# main.net
KiCad netlist of a schematic drawn in Altium Designer
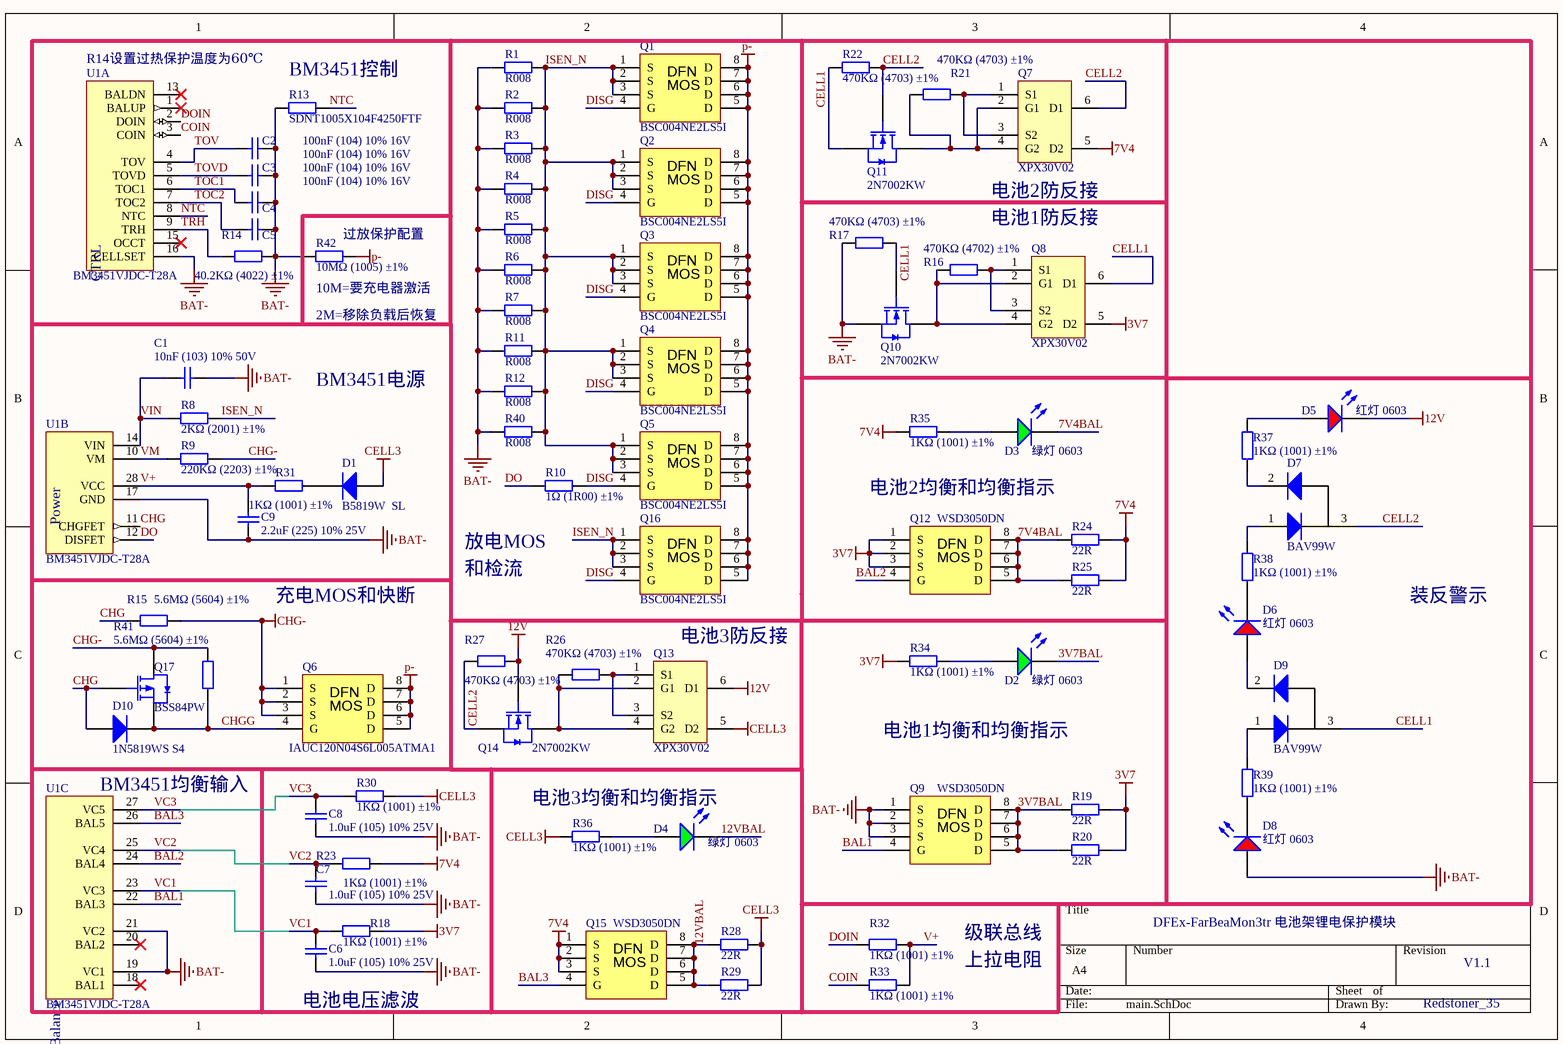
[diagram p0: main.SchDoc]

(export (version "E")
  (design (tool "Eeschema 10.0.6"))
  (components
    (comp (ref "C1")
      (value "10nF (103) 10% 50V")
      (footprint "0402_C")
      (description "贴片电容")
      (libsource (lib "Miscellaneous Devices LC") (part "0402 10nF (103) 10% 50V"))
    )
    (comp (ref "C2")
      (value "100nF (104) 10% 16V")
      (footprint "0402_C")
      (description "贴片电容")
      (libsource (lib "Miscellaneous Devices LC") (part "0402 100nF (104) 10% 16V"))
    )
    (comp (ref "C3")
      (value "100nF (104) 10% 16V")
      (footprint "0402_C")
      (description "贴片电容")
      (libsource (lib "Miscellaneous Devices LC") (part "0402 100nF (104) 10% 16V"))
    )
    (comp (ref "C4")
      (value "100nF (104) 10% 16V")
      (footprint "0402_C")
      (description "贴片电容")
      (libsource (lib "Miscellaneous Devices LC") (part "0402 100nF (104) 10% 16V"))
    )
    (comp (ref "C5")
      (value "100nF (104) 10% 16V")
      (footprint "0402_C")
      (description "贴片电容")
      (libsource (lib "Miscellaneous Devices LC") (part "0402 100nF (104) 10% 16V"))
    )
    (comp (ref "C6")
      (value "1.0uF (105) 10% 25V")
      (footprint "0402_C")
      (description "贴片电容")
      (libsource (lib "Miscellaneous Devices LC") (part "0402 1.0uF (105) 10% 25V"))
    )
    (comp (ref "C7")
      (value "1.0uF (105) 10% 25V")
      (footprint "0402_C")
      (description "贴片电容")
      (libsource (lib "Miscellaneous Devices LC") (part "0402 1.0uF (105) 10% 25V"))
    )
    (comp (ref "C8")
      (value "1.0uF (105) 10% 25V")
      (footprint "0402_C")
      (description "贴片电容")
      (libsource (lib "Miscellaneous Devices LC") (part "0402 1.0uF (105) 10% 25V"))
    )
    (comp (ref "C9")
      (value "2.2uF (225) 10% 25V")
      (footprint "0402_C")
      (description "贴片电容")
      (libsource (lib "Miscellaneous Devices LC") (part "0402 2.2nF (222) 10% 50V"))
    )
    (comp (ref "D1")
      (value "B5819W  SL")
      (footprint "SOD-123")
      (description "肖特基二极管")
      (libsource (lib "Miscellaneous Devices LC") (part "SOD-123 B5819W  SL"))
    )
    (comp (ref "D2")
      (value "绿灯 0603")
      (footprint "0603_LED_S1")
      (description "发光二极管")
      (libsource (lib "Miscellaneous Devices LC") (part "0603 绿灯"))
    )
    (comp (ref "D3")
      (value "绿灯 0603")
      (footprint "0603_LED_S1")
      (description "发光二极管")
      (libsource (lib "Miscellaneous Devices LC") (part "0603 绿灯"))
    )
    (comp (ref "D4")
      (value "绿灯 0603")
      (footprint "0603_LED_S1")
      (description "发光二极管")
      (libsource (lib "Miscellaneous Devices LC") (part "0603 绿灯"))
    )
    (comp (ref "D5")
      (value "红灯 0603")
      (footprint "0603_LED_S1")
      (description "发光二极管")
      (libsource (lib "Miscellaneous Devices LC") (part "0603 红灯"))
    )
    (comp (ref "D6")
      (value "红灯 0603")
      (footprint "0603_LED_S1")
      (description "发光二极管")
      (libsource (lib "Miscellaneous Devices LC") (part "0603 红灯"))
    )
    (comp (ref "D7")
      (value "BAV99W")
      (footprint "SC70-3")
      (description "开关二极管")
      (libsource (lib "Miscellaneous Devices LC") (part "SOT-23 BAV99 A7W"))
    )
    (comp (ref "D8")
      (value "红灯 0603")
      (footprint "0603_LED_S1")
      (description "发光二极管")
      (libsource (lib "Miscellaneous Devices LC") (part "0603 红灯"))
    )
    (comp (ref "D9")
      (value "BAV99W")
      (footprint "SC70-3")
      (description "开关二极管")
      (libsource (lib "Miscellaneous Devices LC") (part "SOT-23 BAV99 A7W"))
    )
    (comp (ref "D10")
      (value "1N5819WS S4")
      (footprint "SOD-323")
      (description "二极管")
      (libsource (lib "Miscellaneous Devices LC") (part "SOD-323 1N4148WS T4"))
    )
    (comp (ref "Q1")
      (value "BSC004NE2LS5I")
      (footprint "SON/DFN5x6(MOS)")
      (description "0.4mR OptiMOS 5 MOSFET")
      (libsource (lib "custom") (part "SON/DFN5x6 MOS"))
    )
    (comp (ref "Q2")
      (value "BSC004NE2LS5I")
      (footprint "SON/DFN5x6(MOS)")
      (description "0.4mR OptiMOS 5 MOSFET")
      (libsource (lib "custom") (part "SON/DFN5x6 MOS"))
    )
    (comp (ref "Q3")
      (value "BSC004NE2LS5I")
      (footprint "SON/DFN5x6(MOS)")
      (description "0.4mR OptiMOS 5 MOSFET")
      (libsource (lib "custom") (part "SON/DFN5x6 MOS"))
    )
    (comp (ref "Q4")
      (value "BSC004NE2LS5I")
      (footprint "SON/DFN5x6(MOS)")
      (description "0.4mR OptiMOS 5 MOSFET")
      (libsource (lib "custom") (part "SON/DFN5x6 MOS"))
    )
    (comp (ref "Q5")
      (value "BSC004NE2LS5I")
      (footprint "SON/DFN5x6(MOS)")
      (description "0.4mR OptiMOS 5 MOSFET")
      (libsource (lib "custom") (part "SON/DFN5x6 MOS"))
    )
    (comp (ref "Q6")
      (value "IAUC120N04S6L005ATMA1")
      (footprint "SON/DFN5x6(MOS)")
      (description "0.5mR 120A OptiMOS 6 Automotive grade MOSFET,SSO8(5x6) Package")
      (libsource (lib "custom") (part "SON/DFN5x6 MOS"))
    )
    (comp (ref "Q7")
      (value "XPX30V02")
      (footprint "EDFN3x3")
      (description "双N沟道MOSFET, DFN3x3 30V 40A 10mΩ")
      (libsource (lib "custom") (part "XPX10H03RX"))
    )
    (comp (ref "Q8")
      (value "XPX30V02")
      (footprint "EDFN3x3")
      (description "双N沟道MOSFET, DFN3x3 30V 40A 10mΩ")
      (libsource (lib "custom") (part "XPX10H03RX"))
    )
    (comp (ref "Q9")
      (value "WSD3050DN")
      (footprint "DFN-8_L3.0-W3.0-P0.65-BL")
      (description "PDFN3x3 20V 50A 5.8mΩ N-Ch MOSFET")
      (libsource (lib "custom") (part "SON/DFN5x6 MOS"))
    )
    (comp (ref "Q10")
      (value "2N7002KW")
      (footprint "SC70-3")
      (description "单N沟道MOSFET(场效应管)")
      (libsource (lib "Miscellaneous Devices LC") (part "2N7002 7002"))
    )
    (comp (ref "Q11")
      (value "2N7002KW")
      (footprint "SC70-3")
      (description "单N沟道MOSFET(场效应管)")
      (libsource (lib "Miscellaneous Devices LC") (part "2N7002 7002"))
    )
    (comp (ref "Q12")
      (value "WSD3050DN")
      (footprint "DFN-8_L3.0-W3.0-P0.65-BL")
      (description "PDFN3x3 20V 50A 5.8mΩ N-Ch MOSFET")
      (libsource (lib "custom") (part "SON/DFN5x6 MOS"))
    )
    (comp (ref "Q13")
      (value "XPX30V02")
      (footprint "EDFN3x3")
      (description "双N沟道MOSFET, DFN3x3 30V 40A 10mΩ")
      (libsource (lib "custom") (part "XPX10H03RX"))
    )
    (comp (ref "Q14")
      (value "2N7002KW")
      (footprint "SC70-3")
      (description "单N沟道MOSFET(场效应管)")
      (libsource (lib "Miscellaneous Devices LC") (part "2N7002 7002"))
    )
    (comp (ref "Q15")
      (value "WSD3050DN")
      (footprint "DFN-8_L3.0-W3.0-P0.65-BL")
      (description "PDFN3x3 20V 50A 5.8mΩ N-Ch MOSFET")
      (libsource (lib "custom") (part "SON/DFN5x6 MOS"))
    )
    (comp (ref "Q16")
      (value "BSC004NE2LS5I")
      (footprint "SON/DFN5x6(MOS)")
      (description "0.4mR OptiMOS 5 MOSFET")
      (libsource (lib "custom") (part "SON/DFN5x6 MOS"))
    )
    (comp (ref "Q17")
      (value "BSS84PW")
      (footprint "SC70-3")
      (description "MOS(场效应管)")
      (libsource (lib "Miscellaneous Devices LC") (part "SI2301CDS-T1-GE3"))
    )
    (comp (ref "R1")
      (value "R008")
      (footprint "1206R")
      (description "Resistor")
      (fields (field (name "PUBLISHER") "Altium Limited"))
      (libsource (lib "山猫的集成库20190318") (part "Res"))
    )
    (comp (ref "R2")
      (value "R008")
      (footprint "1206R")
      (description "Resistor")
      (fields (field (name "PUBLISHER") "Altium Limited"))
      (libsource (lib "山猫的集成库20190318") (part "Res"))
    )
    (comp (ref "R3")
      (value "R008")
      (footprint "1206R")
      (description "Resistor")
      (fields (field (name "PUBLISHER") "Altium Limited"))
      (libsource (lib "山猫的集成库20190318") (part "Res"))
    )
    (comp (ref "R4")
      (value "R008")
      (footprint "1206R")
      (description "Resistor")
      (fields (field (name "PUBLISHER") "Altium Limited"))
      (libsource (lib "山猫的集成库20190318") (part "Res"))
    )
    (comp (ref "R5")
      (value "R008")
      (footprint "1206R")
      (description "Resistor")
      (fields (field (name "PUBLISHER") "Altium Limited"))
      (libsource (lib "山猫的集成库20190318") (part "Res"))
    )
    (comp (ref "R6")
      (value "R008")
      (footprint "1206R")
      (description "Resistor")
      (fields (field (name "PUBLISHER") "Altium Limited"))
      (libsource (lib "山猫的集成库20190318") (part "Res"))
    )
    (comp (ref "R7")
      (value "R008")
      (footprint "1206R")
      (description "Resistor")
      (fields (field (name "PUBLISHER") "Altium Limited"))
      (libsource (lib "山猫的集成库20190318") (part "Res"))
    )
    (comp (ref "R8")
      (value "2KΩ (2001) ±1%")
      (footprint "0402_R")
      (description "贴片电阻")
      (libsource (lib "Miscellaneous Devices LC") (part "0402 2KΩ (2001) 1%"))
    )
    (comp (ref "R9")
      (value "220KΩ (2203) ±1%")
      (footprint "0402_R")
      (description "贴片电阻")
      (libsource (lib "Miscellaneous Devices LC") (part "0402 220KΩ (2203) 1%"))
    )
    (comp (ref "R10")
      (value "1Ω (1R00) ±1%")
      (footprint "0402_R")
      (description "贴片电阻")
      (libsource (lib "Miscellaneous Devices LC") (part "0402 1Ω (1R00) 1%"))
    )
    (comp (ref "R11")
      (value "R008")
      (footprint "1206R")
      (description "Resistor")
      (fields (field (name "PUBLISHER") "Altium Limited"))
      (libsource (lib "山猫的集成库20190318") (part "Res"))
    )
    (comp (ref "R12")
      (value "R008")
      (footprint "1206R")
      (description "Resistor")
      (fields (field (name "PUBLISHER") "Altium Limited"))
      (libsource (lib "山猫的集成库20190318") (part "Res"))
    )
    (comp (ref "R13")
      (value "SDNT1005X104F4250FTF")
      (footprint "0402_R")
      (description "贴片NTC热敏电阻 100KΩ (1003) ±1% B4250")
      (libsource (lib "Miscellaneous Devices LC") (part "0402 100KΩ (1003) 1%"))
    )
    (comp (ref "R14")
      (value "40.2KΩ (4022) ±1%")
      (footprint "0402_R")
      (description "贴片电阻")
      (libsource (lib "Miscellaneous Devices LC") (part "0402 56KΩ (5602) 1%"))
    )
    (comp (ref "R15")
      (value "5.6MΩ (5604) ±1%")
      (footprint "0402_R")
      (description "贴片电阻")
      (libsource (lib "") (part "0402 1MΩ (1004) 1%_1"))
    )
    (comp (ref "R16")
      (value "470KΩ (4702) ±1%")
      (footprint "0402_R")
      (description "贴片电阻")
      (libsource (lib "Miscellaneous Devices LC") (part "0402 20KΩ (2002) 1%"))
    )
    (comp (ref "R17")
      (value "470KΩ (4703) ±1%")
      (footprint "0402_R")
      (description "贴片电阻")
      (libsource (lib "Miscellaneous Devices LC") (part "0402 470KΩ (4703) 1%"))
    )
    (comp (ref "R18")
      (value "1KΩ (1001) ±1%")
      (footprint "0402_R")
      (description "贴片电阻")
      (libsource (lib "Miscellaneous Devices LC") (part "0402 1KΩ (1001) 1%"))
    )
    (comp (ref "R19")
      (value "22R")
      (footprint "1210R")
      (description "Resistor")
      (fields (field (name "PUBLISHER") "Altium Limited"))
      (libsource (lib "山猫的集成库20190318") (part "Res"))
    )
    (comp (ref "R20")
      (value "22R")
      (footprint "1210R")
      (description "Resistor")
      (fields (field (name "PUBLISHER") "Altium Limited"))
      (libsource (lib "山猫的集成库20190318") (part "Res"))
    )
    (comp (ref "R21")
      (value "470KΩ (4703) ±1%")
      (footprint "0402_R")
      (description "贴片电阻")
      (libsource (lib "Miscellaneous Devices LC") (part "0402 470KΩ (4703) 1%"))
    )
    (comp (ref "R22")
      (value "470KΩ (4703) ±1%")
      (footprint "0402_R")
      (description "贴片电阻")
      (libsource (lib "Miscellaneous Devices LC") (part "0402 470KΩ (4703) 1%"))
    )
    (comp (ref "R23")
      (value "1KΩ (1001) ±1%")
      (footprint "0402_R")
      (description "贴片电阻")
      (libsource (lib "Miscellaneous Devices LC") (part "0402 1KΩ (1001) 1%"))
    )
    (comp (ref "R24")
      (value "22R")
      (footprint "1210R")
      (description "Resistor")
      (fields (field (name "PUBLISHER") "Altium Limited"))
      (libsource (lib "山猫的集成库20190318") (part "Res"))
    )
    (comp (ref "R25")
      (value "22R")
      (footprint "1210R")
      (description "Resistor")
      (fields (field (name "PUBLISHER") "Altium Limited"))
      (libsource (lib "山猫的集成库20190318") (part "Res"))
    )
    (comp (ref "R26")
      (value "470KΩ (4703) ±1%")
      (footprint "0402_R")
      (description "贴片电阻")
      (libsource (lib "Miscellaneous Devices LC") (part "0402 470KΩ (4703) 1%"))
    )
    (comp (ref "R27")
      (value "470KΩ (4703) ±1%")
      (footprint "0402_R")
      (description "贴片电阻")
      (libsource (lib "Miscellaneous Devices LC") (part "0402 470KΩ (4703) 1%"))
    )
    (comp (ref "R28")
      (value "22R")
      (footprint "1210R")
      (description "Resistor")
      (fields (field (name "PUBLISHER") "Altium Limited"))
      (libsource (lib "山猫的集成库20190318") (part "Res"))
    )
    (comp (ref "R29")
      (value "22R")
      (footprint "1210R")
      (description "Resistor")
      (fields (field (name "PUBLISHER") "Altium Limited"))
      (libsource (lib "山猫的集成库20190318") (part "Res"))
    )
    (comp (ref "R30")
      (value "1KΩ (1001) ±1%")
      (footprint "0402_R")
      (description "贴片电阻")
      (libsource (lib "Miscellaneous Devices LC") (part "0402 1KΩ (1001) 1%"))
    )
    (comp (ref "R31")
      (value "1KΩ (1001) ±1%")
      (footprint "0402_R")
      (description "贴片电阻")
      (libsource (lib "Miscellaneous Devices LC") (part "0402 1KΩ (1001) 1%"))
    )
    (comp (ref "R32")
      (value "1KΩ (1001) ±1%")
      (footprint "0402_R")
      (description "贴片电阻")
      (libsource (lib "Miscellaneous Devices LC") (part "0402 1KΩ (1001) 1%"))
    )
    (comp (ref "R33")
      (value "1KΩ (1001) ±1%")
      (footprint "0402_R")
      (description "贴片电阻")
      (libsource (lib "Miscellaneous Devices LC") (part "0402 1KΩ (1001) 1%"))
    )
    (comp (ref "R34")
      (value "1KΩ (1001) ±1%")
      (footprint "0402_R")
      (description "贴片电阻")
      (libsource (lib "Miscellaneous Devices LC") (part "0402 1KΩ (1001) 1%"))
    )
    (comp (ref "R35")
      (value "1KΩ (1001) ±1%")
      (footprint "0402_R")
      (description "贴片电阻")
      (libsource (lib "Miscellaneous Devices LC") (part "0402 1KΩ (1001) 1%"))
    )
    (comp (ref "R36")
      (value "1KΩ (1001) ±1%")
      (footprint "0402_R")
      (description "贴片电阻")
      (libsource (lib "Miscellaneous Devices LC") (part "0402 1KΩ (1001) 1%"))
    )
    (comp (ref "R37")
      (value "1KΩ (1001) ±1%")
      (footprint "0402_R")
      (description "贴片电阻")
      (libsource (lib "") (part "0402 1KΩ (1001) 1%_1"))
    )
    (comp (ref "R38")
      (value "1KΩ (1001) ±1%")
      (footprint "0402_R")
      (description "贴片电阻")
      (libsource (lib "") (part "0402 1KΩ (1001) 1%_1"))
    )
    (comp (ref "R39")
      (value "1KΩ (1001) ±1%")
      (footprint "0402_R")
      (description "贴片电阻")
      (libsource (lib "") (part "0402 1KΩ (1001) 1%_1"))
    )
    (comp (ref "R40")
      (value "R008")
      (footprint "1206R")
      (description "Resistor")
      (fields (field (name "PUBLISHER") "Altium Limited"))
      (libsource (lib "山猫的集成库20190318") (part "Res"))
    )
    (comp (ref "R41")
      (value "5.6MΩ (5604) ±1%")
      (footprint "0402_R")
      (description "贴片电阻")
      (libsource (lib "Miscellaneous Devices LC") (part "0402 1MΩ (1004) 1%"))
    )
    (comp (ref "R42")
      (value "10MΩ (1005) ±1%")
      (footprint "0402_R")
      (description "贴片电阻")
      (libsource (lib "Miscellaneous Devices LC") (part "0402 10MΩ (1005) 1%"))
    )
    (comp (ref "U1")
      (value "BM3451VJDC-T28A")
      (footprint "TSSOP28-BM3451")
      (description "2-5串全功能锂电池保护IC，支持级联功能")
      (libsource (lib "custom") (part "BM3451-T28A"))
    )
  )
  (nets
    (net (code "1") (name "/3V7BAL") (class "Default")
      (node (ref "D2") (pin "K") (pinfunction "K_K") (pintype "passive"))
      (node (ref "Q9") (pin "5") (pinfunction "D_5") (pintype "passive"))
      (node (ref "Q9") (pin "6") (pinfunction "D_6") (pintype "passive"))
      (node (ref "Q9") (pin "7") (pinfunction "D_7") (pintype "passive"))
      (node (ref "Q9") (pin "8") (pinfunction "D_8") (pintype "passive"))
      (node (ref "R19") (pin "2") (pinfunction "2_2") (pintype "passive"))
      (node (ref "R20") (pin "2") (pinfunction "2_2") (pintype "passive"))
    )
    (net (code "2") (name "/7V4BAL") (class "Default")
      (node (ref "D3") (pin "K") (pinfunction "K_K") (pintype "passive"))
      (node (ref "Q12") (pin "5") (pinfunction "D_5") (pintype "passive"))
      (node (ref "Q12") (pin "6") (pinfunction "D_6") (pintype "passive"))
      (node (ref "Q12") (pin "7") (pinfunction "D_7") (pintype "passive"))
      (node (ref "Q12") (pin "8") (pinfunction "D_8") (pintype "passive"))
      (node (ref "R24") (pin "2") (pinfunction "2_2") (pintype "passive"))
      (node (ref "R25") (pin "2") (pinfunction "2_2") (pintype "passive"))
    )
    (net (code "3") (name "/12VBAL") (class "Default")
      (node (ref "D4") (pin "K") (pinfunction "K_K") (pintype "passive"))
      (node (ref "Q15") (pin "5") (pinfunction "D_5") (pintype "passive"))
      (node (ref "Q15") (pin "6") (pinfunction "D_6") (pintype "passive"))
      (node (ref "Q15") (pin "7") (pinfunction "D_7") (pintype "passive"))
      (node (ref "Q15") (pin "8") (pinfunction "D_8") (pintype "passive"))
      (node (ref "R28") (pin "2") (pinfunction "2_2") (pintype "passive"))
      (node (ref "R29") (pin "2") (pinfunction "2_2") (pintype "passive"))
    )
    (net (code "4") (name "/BAL1") (class "Default")
      (node (ref "Q9") (pin "4") (pinfunction "G_4") (pintype "passive"))
      (node (ref "U1") (pin "22") (pinfunction "BAL3_22") (pintype "power_in"))
    )
    (net (code "5") (name "/BAL2") (class "Default")
      (node (ref "Q12") (pin "4") (pinfunction "G_4") (pintype "passive"))
      (node (ref "U1") (pin "24") (pinfunction "BAL4_24") (pintype "power_in"))
    )
    (net (code "6") (name "/BAL3") (class "Default")
      (node (ref "Q15") (pin "4") (pinfunction "G_4") (pintype "passive"))
      (node (ref "U1") (pin "26") (pinfunction "BAL5_26") (pintype "power_in"))
    )
    (net (code "7") (name "/CELL1") (class "Default")
      (node (ref "D9") (pin "3") (pinfunction "K_3") (pintype "passive"))
      (node (ref "Q10") (pin "1") (pinfunction "G_1") (pintype "passive"))
      (node (ref "Q11") (pin "2") (pinfunction "S_2") (pintype "passive"))
      (node (ref "Q8") (pin "6") (pinfunction "D1_6") (pintype "passive"))
      (node (ref "R17") (pin "2") (pinfunction "2_2") (pintype "passive"))
      (node (ref "R22") (pin "1") (pinfunction "1_1") (pintype "passive"))
    )
    (net (code "8") (name "/CELL2") (class "Default")
      (node (ref "D7") (pin "3") (pinfunction "K_3") (pintype "passive"))
      (node (ref "Q11") (pin "1") (pinfunction "G_1") (pintype "passive"))
      (node (ref "Q14") (pin "2") (pinfunction "S_2") (pintype "passive"))
      (node (ref "Q7") (pin "6") (pinfunction "D1_6") (pintype "passive"))
      (node (ref "R22") (pin "2") (pinfunction "2_2") (pintype "passive"))
      (node (ref "R27") (pin "1") (pinfunction "1_1") (pintype "passive"))
    )
    (net (code "9") (name "/CHG") (class "Default")
      (node (ref "D10") (pin "1") (pinfunction "A_1") (pintype "passive"))
      (node (ref "Q17") (pin "1") (pinfunction "G_1") (pintype "passive"))
      (node (ref "R15") (pin "1") (pinfunction "1_1") (pintype "passive"))
      (node (ref "U1") (pin "11") (pinfunction "CHGFET_11") (pintype "output"))
    )
    (net (code "10") (name "/CHGG") (class "Default")
      (node (ref "D10") (pin "2") (pinfunction "K_2") (pintype "passive"))
      (node (ref "Q17") (pin "2") (pinfunction "S_2") (pintype "passive"))
      (node (ref "Q6") (pin "4") (pinfunction "G_4") (pintype "passive"))
      (node (ref "R41") (pin "1") (pinfunction "1_1") (pintype "passive"))
    )
    (net (code "11") (name "/COIN") (class "Default")
      (node (ref "R33") (pin "1") (pinfunction "1_1") (pintype "passive"))
      (node (ref "U1") (pin "3") (pinfunction "COIN_3") (pintype "bidirectional"))
    )
    (net (code "12") (name "/DISG") (class "Default")
      (node (ref "Q1") (pin "4") (pinfunction "G_4") (pintype "passive"))
      (node (ref "Q16") (pin "4") (pinfunction "G_4") (pintype "passive"))
      (node (ref "Q2") (pin "4") (pinfunction "G_4") (pintype "passive"))
      (node (ref "Q3") (pin "4") (pinfunction "G_4") (pintype "passive"))
      (node (ref "Q4") (pin "4") (pinfunction "G_4") (pintype "passive"))
      (node (ref "Q5") (pin "4") (pinfunction "G_4") (pintype "passive"))
      (node (ref "R10") (pin "2") (pinfunction "2_2") (pintype "passive"))
    )
    (net (code "13") (name "/DO") (class "Default")
      (node (ref "R10") (pin "1") (pinfunction "1_1") (pintype "passive"))
      (node (ref "U1") (pin "12") (pinfunction "DISFET_12") (pintype "output"))
    )
    (net (code "14") (name "/DOIN") (class "Default")
      (node (ref "R32") (pin "1") (pinfunction "1_1") (pintype "passive"))
      (node (ref "U1") (pin "2") (pinfunction "DOIN_2") (pintype "bidirectional"))
    )
    (net (code "15") (name "/ISEN_N") (class "Default")
      (node (ref "Q1") (pin "1") (pinfunction "S_1") (pintype "passive"))
      (node (ref "Q1") (pin "2") (pinfunction "S_2") (pintype "passive"))
      (node (ref "Q1") (pin "3") (pinfunction "S_3") (pintype "passive"))
      (node (ref "Q16") (pin "1") (pinfunction "S_1") (pintype "passive"))
      (node (ref "Q16") (pin "2") (pinfunction "S_2") (pintype "passive"))
      (node (ref "Q16") (pin "3") (pinfunction "S_3") (pintype "passive"))
      (node (ref "Q2") (pin "1") (pinfunction "S_1") (pintype "passive"))
      (node (ref "Q2") (pin "2") (pinfunction "S_2") (pintype "passive"))
      (node (ref "Q2") (pin "3") (pinfunction "S_3") (pintype "passive"))
      (node (ref "Q3") (pin "1") (pinfunction "S_1") (pintype "passive"))
      (node (ref "Q3") (pin "2") (pinfunction "S_2") (pintype "passive"))
      (node (ref "Q3") (pin "3") (pinfunction "S_3") (pintype "passive"))
      (node (ref "Q4") (pin "1") (pinfunction "S_1") (pintype "passive"))
      (node (ref "Q4") (pin "2") (pinfunction "S_2") (pintype "passive"))
      (node (ref "Q4") (pin "3") (pinfunction "S_3") (pintype "passive"))
      (node (ref "Q5") (pin "1") (pinfunction "S_1") (pintype "passive"))
      (node (ref "Q5") (pin "2") (pinfunction "S_2") (pintype "passive"))
      (node (ref "Q5") (pin "3") (pinfunction "S_3") (pintype "passive"))
      (node (ref "R1") (pin "1") (pinfunction "1_1") (pintype "passive"))
      (node (ref "R11") (pin "1") (pinfunction "1_1") (pintype "passive"))
      (node (ref "R12") (pin "1") (pinfunction "1_1") (pintype "passive"))
      (node (ref "R2") (pin "1") (pinfunction "1_1") (pintype "passive"))
      (node (ref "R3") (pin "1") (pinfunction "1_1") (pintype "passive"))
      (node (ref "R4") (pin "1") (pinfunction "1_1") (pintype "passive"))
      (node (ref "R40") (pin "1") (pinfunction "1_1") (pintype "passive"))
      (node (ref "R5") (pin "1") (pinfunction "1_1") (pintype "passive"))
      (node (ref "R6") (pin "1") (pinfunction "1_1") (pintype "passive"))
      (node (ref "R7") (pin "1") (pinfunction "1_1") (pintype "passive"))
      (node (ref "R8") (pin "2") (pinfunction "2_2") (pintype "passive"))
    )
    (net (code "16") (name "/NTC") (class "Default")
      (node (ref "R13") (pin "1") (pinfunction "1_1") (pintype "passive"))
      (node (ref "U1") (pin "8") (pinfunction "NTC_8") (pintype "passive"))
    )
    (net (code "17") (name "/TOC1") (class "Default")
      (node (ref "C4") (pin "1") (pinfunction "1_1") (pintype "passive"))
      (node (ref "U1") (pin "6") (pinfunction "TOC1_6") (pintype "passive"))
    )
    (net (code "18") (name "/TOC2") (class "Default")
      (node (ref "C5") (pin "1") (pinfunction "1_1") (pintype "passive"))
      (node (ref "U1") (pin "7") (pinfunction "TOC2_7") (pintype "passive"))
    )
    (net (code "19") (name "/TOV") (class "Default")
      (node (ref "C2") (pin "1") (pinfunction "1_1") (pintype "passive"))
      (node (ref "U1") (pin "4") (pinfunction "TOV_4") (pintype "passive"))
    )
    (net (code "20") (name "/TOVD") (class "Default")
      (node (ref "C3") (pin "1") (pinfunction "1_1") (pintype "passive"))
      (node (ref "U1") (pin "5") (pinfunction "TOVD_5") (pintype "passive"))
    )
    (net (code "21") (name "/TRH") (class "Default")
      (node (ref "R14") (pin "1") (pinfunction "1_1") (pintype "passive"))
      (node (ref "U1") (pin "9") (pinfunction "TRH_9") (pintype "passive"))
    )
    (net (code "22") (name "/V+") (class "Default")
      (node (ref "C9") (pin "2") (pinfunction "2_2") (pintype "passive"))
      (node (ref "R31") (pin "1") (pinfunction "1_1") (pintype "passive"))
      (node (ref "R32") (pin "2") (pinfunction "2_2") (pintype "passive"))
      (node (ref "R33") (pin "2") (pinfunction "2_2") (pintype "passive"))
      (node (ref "U1") (pin "28") (pinfunction "VCC_28") (pintype "power_in"))
    )
    (net (code "23") (name "/VC1") (class "Default")
      (node (ref "C6") (pin "2") (pinfunction "2_2") (pintype "passive"))
      (node (ref "R18") (pin "1") (pinfunction "1_1") (pintype "passive"))
      (node (ref "U1") (pin "23") (pinfunction "VC3_23") (pintype "power_in"))
    )
    (net (code "24") (name "/VC2") (class "Default")
      (node (ref "C7") (pin "2") (pinfunction "2_2") (pintype "passive"))
      (node (ref "R23") (pin "1") (pinfunction "1_1") (pintype "passive"))
      (node (ref "U1") (pin "25") (pinfunction "VC4_25") (pintype "power_in"))
    )
    (net (code "25") (name "/VC3") (class "Default")
      (node (ref "C8") (pin "2") (pinfunction "2_2") (pintype "passive"))
      (node (ref "R30") (pin "1") (pinfunction "1_1") (pintype "passive"))
      (node (ref "U1") (pin "27") (pinfunction "VC5_27") (pintype "power_in"))
    )
    (net (code "26") (name "/VIN") (class "Default")
      (node (ref "C1") (pin "1") (pinfunction "1_1") (pintype "passive"))
      (node (ref "R8") (pin "1") (pinfunction "1_1") (pintype "passive"))
      (node (ref "U1") (pin "14") (pinfunction "VIN_14") (pintype "power_in"))
    )
    (net (code "27") (name "/VM") (class "Default")
      (node (ref "R9") (pin "1") (pinfunction "1_1") (pintype "passive"))
      (node (ref "U1") (pin "10") (pinfunction "VM_10") (pintype "passive"))
    )
    (net (code "28") (name "3V7") (class "Default")
      (node (ref "Q12") (pin "1") (pinfunction "S_1") (pintype "passive"))
      (node (ref "Q12") (pin "2") (pinfunction "S_2") (pintype "passive"))
      (node (ref "Q12") (pin "3") (pinfunction "S_3") (pintype "passive"))
      (node (ref "Q8") (pin "5") (pinfunction "D2_5") (pintype "passive"))
      (node (ref "R18") (pin "2") (pinfunction "2_2") (pintype "passive"))
      (node (ref "R19") (pin "1") (pinfunction "1_1") (pintype "passive"))
      (node (ref "R20") (pin "1") (pinfunction "1_1") (pintype "passive"))
      (node (ref "R34") (pin "1") (pinfunction "1_1") (pintype "passive"))
    )
    (net (code "29") (name "7V4") (class "Default")
      (node (ref "Q15") (pin "1") (pinfunction "S_1") (pintype "passive"))
      (node (ref "Q15") (pin "2") (pinfunction "S_2") (pintype "passive"))
      (node (ref "Q15") (pin "3") (pinfunction "S_3") (pintype "passive"))
      (node (ref "Q7") (pin "5") (pinfunction "D2_5") (pintype "passive"))
      (node (ref "R23") (pin "2") (pinfunction "2_2") (pintype "passive"))
      (node (ref "R24") (pin "1") (pinfunction "1_1") (pintype "passive"))
      (node (ref "R25") (pin "1") (pinfunction "1_1") (pintype "passive"))
      (node (ref "R35") (pin "1") (pinfunction "1_1") (pintype "passive"))
    )
    (net (code "30") (name "12V") (class "Default")
      (node (ref "D5") (pin "K") (pinfunction "K_K") (pintype "passive"))
      (node (ref "Q13") (pin "6") (pinfunction "D1_6") (pintype "passive"))
      (node (ref "Q14") (pin "1") (pinfunction "G_1") (pintype "passive"))
      (node (ref "R27") (pin "2") (pinfunction "2_2") (pintype "passive"))
    )
    (net (code "31") (name "BAT-") (class "Default")
      (node (ref "C1") (pin "2") (pinfunction "2_2") (pintype "passive"))
      (node (ref "C2") (pin "2") (pinfunction "2_2") (pintype "passive"))
      (node (ref "C3") (pin "2") (pinfunction "2_2") (pintype "passive"))
      (node (ref "C4") (pin "2") (pinfunction "2_2") (pintype "passive"))
      (node (ref "C5") (pin "2") (pinfunction "2_2") (pintype "passive"))
      (node (ref "C6") (pin "1") (pinfunction "1_1") (pintype "passive"))
      (node (ref "C7") (pin "1") (pinfunction "1_1") (pintype "passive"))
      (node (ref "C8") (pin "1") (pinfunction "1_1") (pintype "passive"))
      (node (ref "C9") (pin "1") (pinfunction "1_1") (pintype "passive"))
      (node (ref "D8") (pin "A") (pinfunction "A_A") (pintype "passive"))
      (node (ref "Q10") (pin "2") (pinfunction "S_2") (pintype "passive"))
      (node (ref "Q9") (pin "1") (pinfunction "S_1") (pintype "passive"))
      (node (ref "Q9") (pin "2") (pinfunction "S_2") (pintype "passive"))
      (node (ref "Q9") (pin "3") (pinfunction "S_3") (pintype "passive"))
      (node (ref "R1") (pin "2") (pinfunction "2_2") (pintype "passive"))
      (node (ref "R11") (pin "2") (pinfunction "2_2") (pintype "passive"))
      (node (ref "R12") (pin "2") (pinfunction "2_2") (pintype "passive"))
      (node (ref "R13") (pin "2") (pinfunction "2_2") (pintype "passive"))
      (node (ref "R14") (pin "2") (pinfunction "2_2") (pintype "passive"))
      (node (ref "R17") (pin "1") (pinfunction "1_1") (pintype "passive"))
      (node (ref "R2") (pin "2") (pinfunction "2_2") (pintype "passive"))
      (node (ref "R3") (pin "2") (pinfunction "2_2") (pintype "passive"))
      (node (ref "R4") (pin "2") (pinfunction "2_2") (pintype "passive"))
      (node (ref "R40") (pin "2") (pinfunction "2_2") (pintype "passive"))
      (node (ref "R42") (pin "1") (pinfunction "1_1") (pintype "passive"))
      (node (ref "R5") (pin "2") (pinfunction "2_2") (pintype "passive"))
      (node (ref "R6") (pin "2") (pinfunction "2_2") (pintype "passive"))
      (node (ref "R7") (pin "2") (pinfunction "2_2") (pintype "passive"))
      (node (ref "U1") (pin "16") (pinfunction "CELLSET_16") (pintype "passive"))
      (node (ref "U1") (pin "17") (pinfunction "GND_17") (pintype "passive"))
      (node (ref "U1") (pin "19") (pinfunction "VC1_19") (pintype "power_in"))
      (node (ref "U1") (pin "21") (pinfunction "VC2_21") (pintype "power_in"))
    )
    (net (code "32") (name "CELL3") (class "Default")
      (node (ref "D1") (pin "1") (pinfunction "A_1") (pintype "passive"))
      (node (ref "Q13") (pin "5") (pinfunction "D2_5") (pintype "passive"))
      (node (ref "R28") (pin "1") (pinfunction "1_1") (pintype "passive"))
      (node (ref "R29") (pin "1") (pinfunction "1_1") (pintype "passive"))
      (node (ref "R30") (pin "2") (pinfunction "2_2") (pintype "passive"))
      (node (ref "R36") (pin "1") (pinfunction "1_1") (pintype "passive"))
    )
    (net (code "33") (name "CHG-") (class "Default")
      (node (ref "Q17") (pin "3") (pinfunction "D_3") (pintype "passive"))
      (node (ref "Q6") (pin "1") (pinfunction "S_1") (pintype "passive"))
      (node (ref "Q6") (pin "2") (pinfunction "S_2") (pintype "passive"))
      (node (ref "Q6") (pin "3") (pinfunction "S_3") (pintype "passive"))
      (node (ref "R15") (pin "2") (pinfunction "2_2") (pintype "passive"))
      (node (ref "R41") (pin "2") (pinfunction "2_2") (pintype "passive"))
      (node (ref "R9") (pin "2") (pinfunction "2_2") (pintype "passive"))
    )
    (net (code "34") (name "Net-(D1-K)") (class "Default")
      (node (ref "D1") (pin "2") (pinfunction "K_2") (pintype "passive"))
      (node (ref "R31") (pin "2") (pinfunction "2_2") (pintype "passive"))
    )
    (net (code "35") (name "Net-(D2-PadA)") (class "Default")
      (node (ref "D2") (pin "A") (pinfunction "A_A") (pintype "passive"))
      (node (ref "R34") (pin "2") (pinfunction "2_2") (pintype "passive"))
    )
    (net (code "36") (name "Net-(D3-PadA)") (class "Default")
      (node (ref "D3") (pin "A") (pinfunction "A_A") (pintype "passive"))
      (node (ref "R35") (pin "2") (pinfunction "2_2") (pintype "passive"))
    )
    (net (code "37") (name "Net-(D4-PadA)") (class "Default")
      (node (ref "D4") (pin "A") (pinfunction "A_A") (pintype "passive"))
      (node (ref "R36") (pin "2") (pinfunction "2_2") (pintype "passive"))
    )
    (net (code "38") (name "Net-(D5-PadA)") (class "Default")
      (node (ref "D5") (pin "A") (pinfunction "A_A") (pintype "passive"))
      (node (ref "R37") (pin "2") (pinfunction "2_2") (pintype "passive"))
    )
    (net (code "39") (name "Net-(D6-PadA)") (class "Default")
      (node (ref "D6") (pin "A") (pinfunction "A_A") (pintype "passive"))
      (node (ref "D9") (pin "2") (pinfunction "A_2") (pintype "passive"))
    )
    (net (code "40") (name "Net-(D6-PadK)") (class "Default")
      (node (ref "D6") (pin "K") (pinfunction "K_K") (pintype "passive"))
      (node (ref "R38") (pin "1") (pinfunction "1_1") (pintype "passive"))
    )
    (net (code "41") (name "Net-(D7-A-Pad1)") (class "Default")
      (node (ref "D7") (pin "1") (pinfunction "A_1") (pintype "passive"))
      (node (ref "R38") (pin "2") (pinfunction "2_2") (pintype "passive"))
    )
    (net (code "42") (name "Net-(D7-A-Pad2)") (class "Default")
      (node (ref "D7") (pin "2") (pinfunction "A_2") (pintype "passive"))
      (node (ref "R37") (pin "1") (pinfunction "1_1") (pintype "passive"))
    )
    (net (code "43") (name "Net-(D8-PadK)") (class "Default")
      (node (ref "D8") (pin "K") (pinfunction "K_K") (pintype "passive"))
      (node (ref "R39") (pin "1") (pinfunction "1_1") (pintype "passive"))
    )
    (net (code "44") (name "Net-(D9-A-Pad1)") (class "Default")
      (node (ref "D9") (pin "1") (pinfunction "A_1") (pintype "passive"))
      (node (ref "R39") (pin "2") (pinfunction "2_2") (pintype "passive"))
    )
    (net (code "45") (name "Net-(Q7-S1)") (class "Default")
      (node (ref "Q7") (pin "1") (pinfunction "S1_1") (pintype "passive"))
      (node (ref "Q7") (pin "3") (pinfunction "S2_3") (pintype "passive"))
      (node (ref "R21") (pin "2") (pinfunction "2_2") (pintype "passive"))
    )
    (net (code "46") (name "Net-(Q8-S1)") (class "Default")
      (node (ref "Q8") (pin "1") (pinfunction "S1_1") (pintype "passive"))
      (node (ref "Q8") (pin "3") (pinfunction "S2_3") (pintype "passive"))
      (node (ref "R16") (pin "2") (pinfunction "2_2") (pintype "passive"))
    )
    (net (code "47") (name "Net-(Q10-D)") (class "Default")
      (node (ref "Q10") (pin "3") (pinfunction "D_3") (pintype "passive"))
      (node (ref "Q8") (pin "2") (pinfunction "G1_2") (pintype "passive"))
      (node (ref "Q8") (pin "4") (pinfunction "G2_4") (pintype "passive"))
      (node (ref "R16") (pin "1") (pinfunction "1_1") (pintype "passive"))
    )
    (net (code "48") (name "Net-(Q11-D)") (class "Default")
      (node (ref "Q11") (pin "3") (pinfunction "D_3") (pintype "passive"))
      (node (ref "Q7") (pin "2") (pinfunction "G1_2") (pintype "passive"))
      (node (ref "Q7") (pin "4") (pinfunction "G2_4") (pintype "passive"))
      (node (ref "R21") (pin "1") (pinfunction "1_1") (pintype "passive"))
    )
    (net (code "49") (name "Net-(Q13-G1)") (class "Default")
      (node (ref "Q13") (pin "2") (pinfunction "G1_2") (pintype "passive"))
      (node (ref "Q13") (pin "4") (pinfunction "G2_4") (pintype "passive"))
      (node (ref "Q14") (pin "3") (pinfunction "D_3") (pintype "passive"))
      (node (ref "R26") (pin "1") (pinfunction "1_1") (pintype "passive"))
    )
    (net (code "50") (name "Net-(Q13-S1)") (class "Default")
      (node (ref "Q13") (pin "1") (pinfunction "S1_1") (pintype "passive"))
      (node (ref "Q13") (pin "3") (pinfunction "S2_3") (pintype "passive"))
      (node (ref "R26") (pin "2") (pinfunction "2_2") (pintype "passive"))
    )
    (net (code "51") (name "p-") (class "Default")
      (node (ref "Q1") (pin "5") (pinfunction "D_5") (pintype "passive"))
      (node (ref "Q1") (pin "6") (pinfunction "D_6") (pintype "passive"))
      (node (ref "Q1") (pin "7") (pinfunction "D_7") (pintype "passive"))
      (node (ref "Q1") (pin "8") (pinfunction "D_8") (pintype "passive"))
      (node (ref "Q16") (pin "5") (pinfunction "D_5") (pintype "passive"))
      (node (ref "Q16") (pin "6") (pinfunction "D_6") (pintype "passive"))
      (node (ref "Q16") (pin "7") (pinfunction "D_7") (pintype "passive"))
      (node (ref "Q16") (pin "8") (pinfunction "D_8") (pintype "passive"))
      (node (ref "Q2") (pin "5") (pinfunction "D_5") (pintype "passive"))
      (node (ref "Q2") (pin "6") (pinfunction "D_6") (pintype "passive"))
      (node (ref "Q2") (pin "7") (pinfunction "D_7") (pintype "passive"))
      (node (ref "Q2") (pin "8") (pinfunction "D_8") (pintype "passive"))
      (node (ref "Q3") (pin "5") (pinfunction "D_5") (pintype "passive"))
      (node (ref "Q3") (pin "6") (pinfunction "D_6") (pintype "passive"))
      (node (ref "Q3") (pin "7") (pinfunction "D_7") (pintype "passive"))
      (node (ref "Q3") (pin "8") (pinfunction "D_8") (pintype "passive"))
      (node (ref "Q4") (pin "5") (pinfunction "D_5") (pintype "passive"))
      (node (ref "Q4") (pin "6") (pinfunction "D_6") (pintype "passive"))
      (node (ref "Q4") (pin "7") (pinfunction "D_7") (pintype "passive"))
      (node (ref "Q4") (pin "8") (pinfunction "D_8") (pintype "passive"))
      (node (ref "Q5") (pin "5") (pinfunction "D_5") (pintype "passive"))
      (node (ref "Q5") (pin "6") (pinfunction "D_6") (pintype "passive"))
      (node (ref "Q5") (pin "7") (pinfunction "D_7") (pintype "passive"))
      (node (ref "Q5") (pin "8") (pinfunction "D_8") (pintype "passive"))
      (node (ref "Q6") (pin "5") (pinfunction "D_5") (pintype "passive"))
      (node (ref "Q6") (pin "6") (pinfunction "D_6") (pintype "passive"))
      (node (ref "Q6") (pin "7") (pinfunction "D_7") (pintype "passive"))
      (node (ref "Q6") (pin "8") (pinfunction "D_8") (pintype "passive"))
      (node (ref "R42") (pin "2") (pinfunction "2_2") (pintype "passive"))
    )
    (net (code "52") (name "unconnected-(U1A-BALDN-Pad13)") (class "Default")
      (node (ref "U1") (pin "13") (pinfunction "BALDN_13") (pintype "passive+no_connect"))
    )
    (net (code "53") (name "unconnected-(U1A-BALUP-Pad1)") (class "Default")
      (node (ref "U1") (pin "1") (pinfunction "BALUP_1") (pintype "output+no_connect"))
    )
    (net (code "54") (name "unconnected-(U1A-OCCT-Pad15)") (class "Default")
      (node (ref "U1") (pin "15") (pinfunction "OCCT_15") (pintype "passive+no_connect"))
    )
    (net (code "55") (name "unconnected-(U1C-BAL1-Pad18)") (class "Default")
      (node (ref "U1") (pin "18") (pinfunction "BAL1_18") (pintype "power_in+no_connect"))
    )
    (net (code "56") (name "unconnected-(U1C-BAL2-Pad20)") (class "Default")
      (node (ref "U1") (pin "20") (pinfunction "BAL2_20") (pintype "power_in+no_connect"))
    )
  )
)
